# Led-3V.net
KiCad netlist of a schematic drawn in Altium Designer
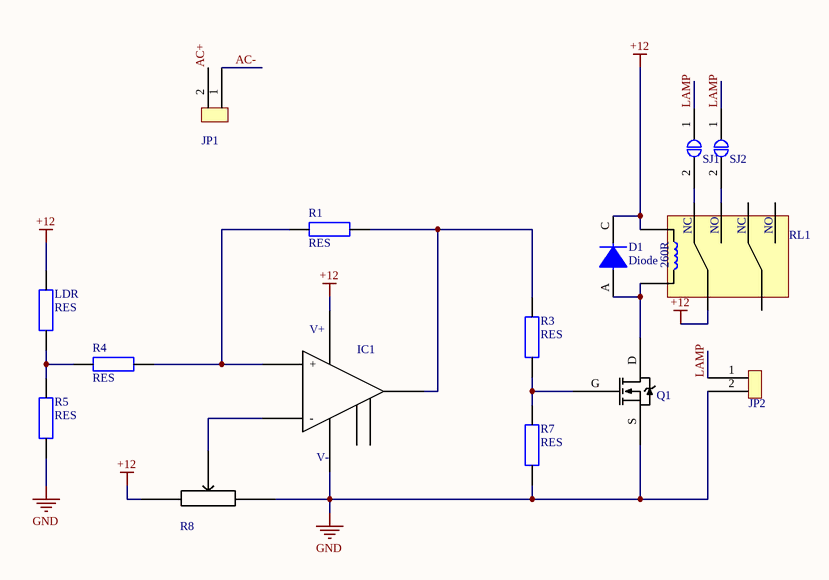
[diagram p0: Led-3V.SchDoc]

(export (version "E")
  (design (tool "Eeschema 10.0.6"))
  (components
    (comp (ref "D1")
      (value "Diode")
      (footprint "DIODE - VERTICAL")
      (libsource (lib "LuongTanDat") (part "Diode"))
    )
    (comp (ref "IC1") (value "lm741-2") (footprint "LM741") (libsource (lib "LuongTanDat") (part "lm741-2")))
    (comp (ref "JP1") (value "JP_2") (footprint "JP_2") (libsource (lib "") (part "JP_2_1")))
    (comp (ref "JP2") (value "JP_2") (footprint "JP_2") (libsource (lib "LuongTanDat") (part "JP_2")))
    (comp (ref "LDR")
      (value "RES")
      (footprint "RES_VERTICAL")
      (description "điện trở size nhỏ")
      (libsource (lib "LuongTanDat") (part "RES"))
    )
    (comp (ref "Q1")
      (value "IRF640")
      (footprint "IRF640")
      (description "Transistor MOSFET N-channel")
      (libsource (lib "LuongTanDat") (part "IRF640"))
    )
    (comp (ref "R1")
      (value "RES")
      (footprint "RES_VERTICAL")
      (description "điện trở size nhỏ")
      (libsource (lib "LuongTanDat") (part "RES"))
    )
    (comp (ref "R3")
      (value "RES")
      (footprint "RES_VERTICAL")
      (description "điện trở size nhỏ")
      (libsource (lib "LuongTanDat") (part "RES"))
    )
    (comp (ref "R4")
      (value "RES")
      (footprint "RES_VERTICAL")
      (description "điện trở size nhỏ")
      (libsource (lib "LuongTanDat") (part "RES"))
    )
    (comp (ref "R5")
      (value "RES")
      (footprint "RES")
      (description "điện trở size nhỏ")
      (libsource (lib "LuongTanDat") (part "RES"))
    )
    (comp (ref "R7")
      (value "RES")
      (footprint "RES_VERTICAL")
      (description "điện trở size nhỏ")
      (libsource (lib "LuongTanDat") (part "RES"))
    )
    (comp (ref "R8")
      (value "POT_RES")
      (footprint "POT_2")
      (description "Potentiometer")
      (libsource (lib "LuongTanDat") (part "POT_RES"))
    )
    (comp (ref "RL1") (value "RYxW-K") (footprint "RYxW-K") (libsource (lib "LuongTanDat") (part "RYxW-K")))
    (comp (ref "SJ1")
      (value "Solderable Jump")
      (footprint "S_JP_1")
      (libsource (lib "LuongTanDat") (part "Solderable Jump"))
    )
    (comp (ref "SJ2")
      (value "Solderable Jump")
      (footprint "S_JP_1")
      (libsource (lib "LuongTanDat") (part "Solderable Jump"))
    )
  )
  (nets
    (net (code "1") (name "+12") (class "Default")
      (node (ref "D1") (pin "C") (pinfunction "2_C") (pintype "passive"))
      (node (ref "IC1") (pin "7") (pinfunction "V+_7") (pintype "passive"))
      (node (ref "LDR") (pin "1") (pinfunction "1_1") (pintype "passive"))
      (node (ref "R8") (pin "1") (pintype "passive"))
      (node (ref "RL1") (pin "1") (pinfunction "1_1") (pintype "passive"))
      (node (ref "RL1") (pin "2") (pinfunction "COM_2") (pintype "passive"))
    )
    (net (code "2") (name "/AC+") (class "Default")
      (node (ref "JP1") (pin "2") (pinfunction "2_2") (pintype "passive"))
    )
    (net (code "3") (name "/AC-") (class "Default")
      (node (ref "JP1") (pin "1") (pinfunction "1_1") (pintype "passive"))
    )
    (net (code "4") (name "/LAMP") (class "Default")
      (node (ref "JP2") (pin "1") (pinfunction "1_1") (pintype "passive"))
      (node (ref "SJ1") (pin "1") (pinfunction "1_1") (pintype "passive"))
      (node (ref "SJ2") (pin "1") (pinfunction "1_1") (pintype "passive"))
    )
    (net (code "5") (name "GND") (class "Default")
      (node (ref "IC1") (pin "4") (pinfunction "V-_4") (pintype "passive"))
      (node (ref "JP2") (pin "2") (pinfunction "2_2") (pintype "passive"))
      (node (ref "Q1") (pin "S") (pinfunction "S_S") (pintype "passive"))
      (node (ref "R5") (pin "1") (pinfunction "1_1") (pintype "passive"))
      (node (ref "R7") (pin "1") (pinfunction "1_1") (pintype "passive"))
      (node (ref "R8") (pin "3") (pinfunction "3_3") (pintype "passive"))
    )
    (net (code "6") (name "Net-(D1-1)") (class "Default")
      (node (ref "D1") (pin "A") (pinfunction "1_A") (pintype "passive"))
      (node (ref "Q1") (pin "D") (pinfunction "D_D") (pintype "passive"))
      (node (ref "RL1") (pin "8") (pinfunction "8_8") (pintype "passive"))
    )
    (net (code "7") (name "Net-(IC1-+)") (class "Default")
      (node (ref "IC1") (pin "3") (pinfunction "+_3") (pintype "passive"))
      (node (ref "R1") (pin "1") (pinfunction "1_1") (pintype "passive"))
      (node (ref "R4") (pin "2") (pinfunction "2_2") (pintype "passive"))
    )
    (net (code "8") (name "Net-(IC1--)") (class "Default")
      (node (ref "IC1") (pin "2") (pinfunction "-_2") (pintype "passive"))
      (node (ref "R8") (pin "2") (pintype "passive"))
    )
    (net (code "9") (name "Net-(IC1-Out)") (class "Default")
      (node (ref "IC1") (pin "6") (pinfunction "Out_6") (pintype "passive"))
      (node (ref "R1") (pin "2") (pinfunction "2_2") (pintype "passive"))
      (node (ref "R3") (pin "2") (pinfunction "2_2") (pintype "passive"))
    )
    (net (code "10") (name "Net-(LDR-Pad2)") (class "Default")
      (node (ref "LDR") (pin "2") (pinfunction "2_2") (pintype "passive"))
      (node (ref "R4") (pin "1") (pinfunction "1_1") (pintype "passive"))
      (node (ref "R5") (pin "2") (pinfunction "2_2") (pintype "passive"))
    )
    (net (code "11") (name "Net-(Q1-PadG)") (class "Default")
      (node (ref "Q1") (pin "G") (pinfunction "G_G") (pintype "passive"))
      (node (ref "R3") (pin "1") (pinfunction "1_1") (pintype "passive"))
      (node (ref "R7") (pin "2") (pinfunction "2_2") (pintype "passive"))
    )
    (net (code "12") (name "Net-(RL1-Pad3)") (class "Default")
      (node (ref "RL1") (pin "3") (pinfunction "3_3") (pintype "passive"))
      (node (ref "SJ1") (pin "2") (pinfunction "2_2") (pintype "passive"))
    )
    (net (code "13") (name "Net-(RL1-Pad4)") (class "Default")
      (node (ref "RL1") (pin "4") (pinfunction "4_4") (pintype "passive"))
      (node (ref "SJ2") (pin "2") (pinfunction "2_2") (pintype "passive"))
    )
    (net (code "14") (name "unconnected-(IC1-Pad1)") (class "Default")
      (node (ref "IC1") (pin "1") (pintype "passive"))
    )
    (net (code "15") (name "unconnected-(IC1-Pad4)") (class "Default")
      (node (ref "IC1") (pin "4") (pintype "passive"))
    )
    (net (code "16") (name "unconnected-(RL1-Pad5)") (class "Default")
      (node (ref "RL1") (pin "5") (pinfunction "5_5") (pintype "passive"))
    )
    (net (code "17") (name "unconnected-(RL1-Pad6)") (class "Default")
      (node (ref "RL1") (pin "6") (pinfunction "6_6") (pintype "passive"))
    )
    (net (code "18") (name "unconnected-(RL1-Pad7)") (class "Default")
      (node (ref "RL1") (pin "7") (pinfunction "7_7") (pintype "passive"))
    )
  )
)
